# unicorder-temp-mk-2_1.net
KiCad netlist of a schematic drawn in EAGLE
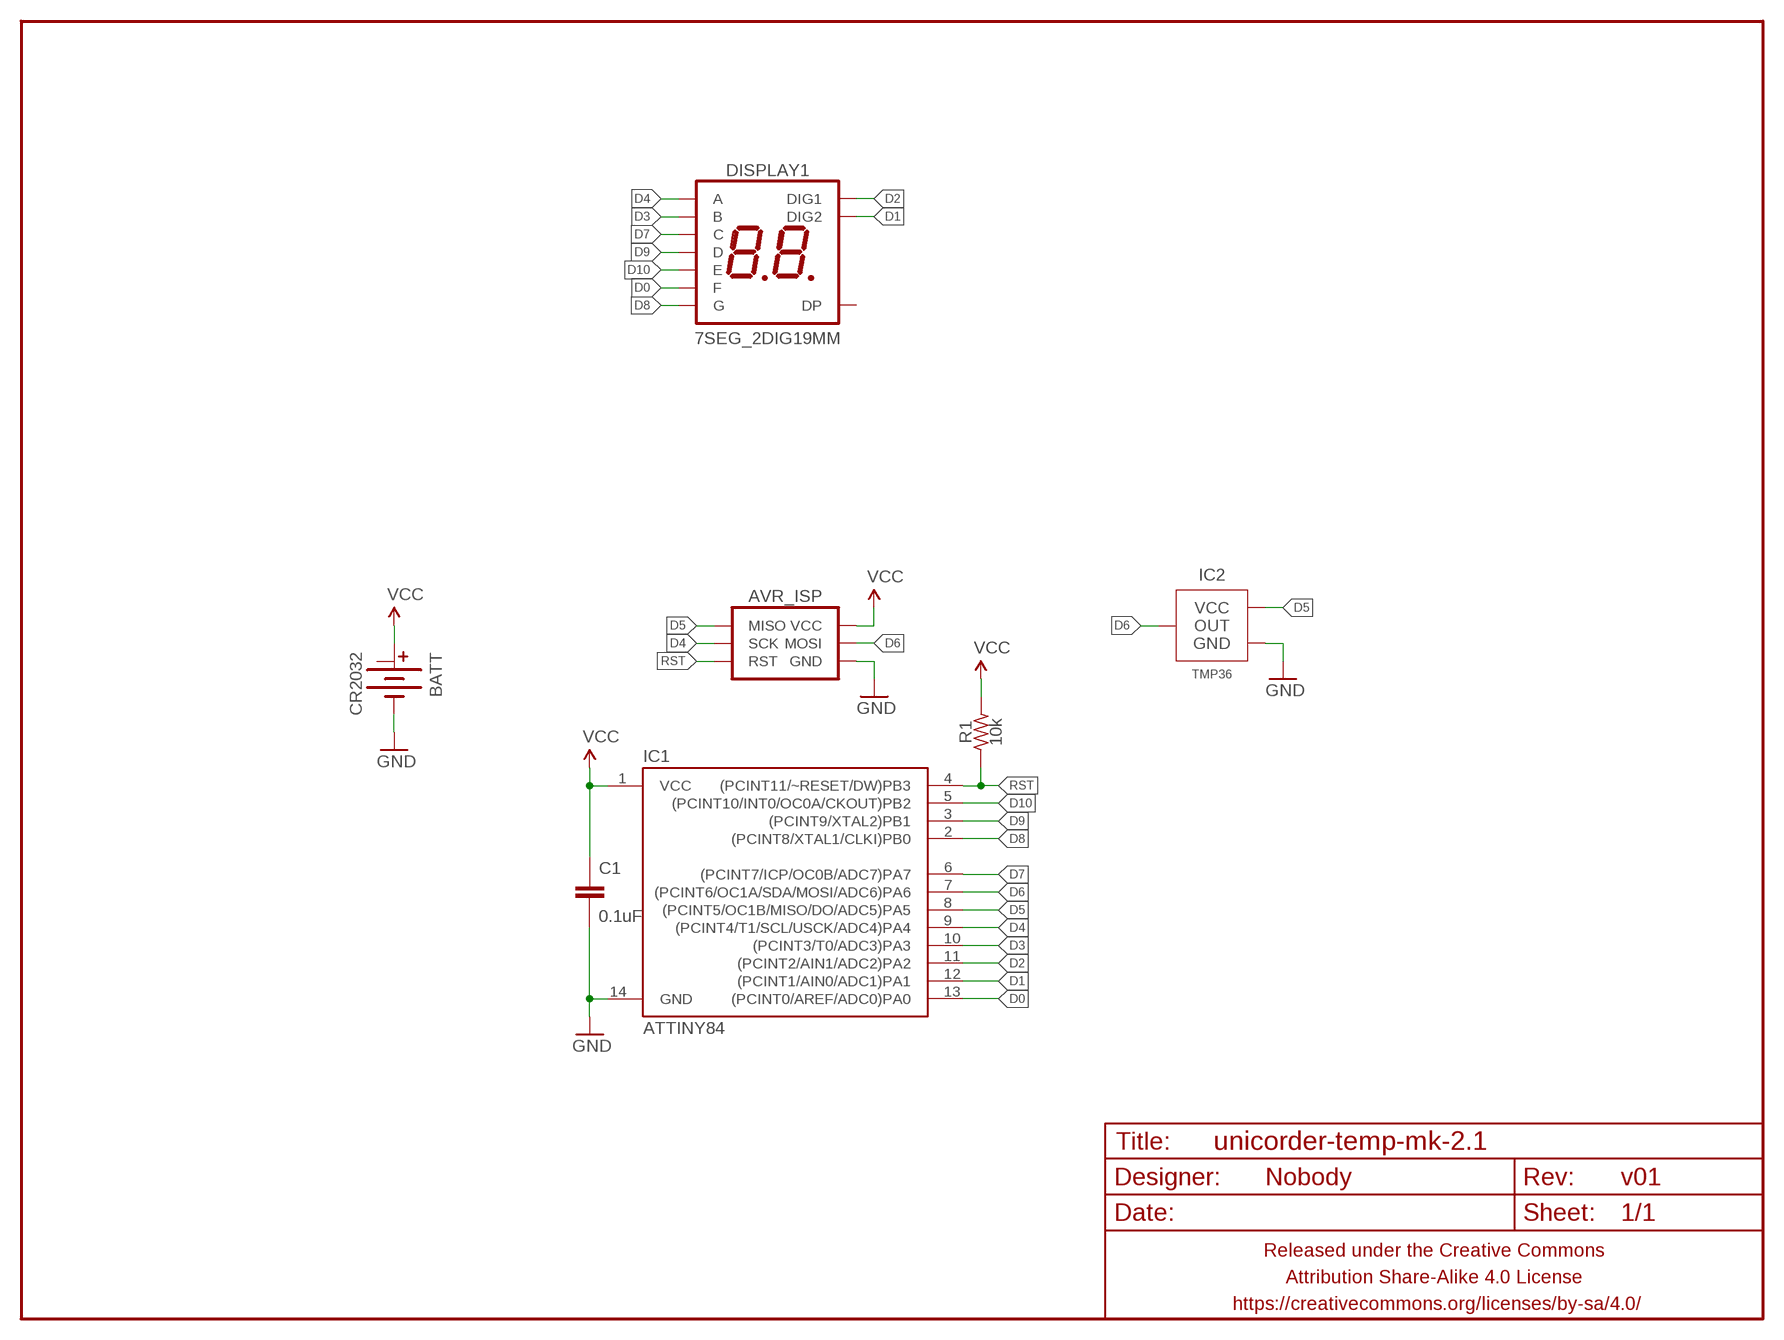
[diagram p0: schematic, sheet 1]

(export (version "E")
  (design (tool "Eeschema 10.0.6"))
  (components
    (comp (ref "AVR_ISP")
      (value "AVR_SPI_PRG_6JST-PH-VERT-PTH")
      (footprint "eagle-import:JST-6-PH-VERT-PTH")
      (libsource (lib "eagle-import") (part "AVR_SPI_PRG_6JST-PH-VERT-PTH"))
    )
    (comp (ref "BATT")
      (value "CR2032")
      (footprint "eagle-import:BATTCON_20MM_MINE")
      (libsource (lib "eagle-import") (part "BATTERY-COINCR2032_SMD"))
    )
    (comp (ref "C1")
      (value "0.1uF")
      (footprint "eagle-import:C025-024X044")
      (libsource (lib "eagle-import") (part "CAPACITOR-CERAMIC025-024X044"))
    )
    (comp (ref "DISPLAY1")
      (value "7SEG_2DIG19MM")
      (footprint "eagle-import:7SEG_2DIG_19MM")
      (libsource (lib "eagle-import") (part "7SEG_2DIG19MM"))
    )
    (comp (ref "FRAME1")
      (value "FRAME-LETTERNO_PACKAGE")
      (footprint "eagle-import:DUMMY")
      (fields (field (name "DESIGNER") "Nobody"))
      (libsource (lib "eagle-import") (part "FRAME-LETTERNO_PACKAGE"))
    )
    (comp (ref "IC1")
      (value "ATTINY84")
      (footprint "eagle-import:DIL14")
      (libsource (lib "eagle-import") (part "ATTINY84ATTINY84-20PU"))
    )
    (comp (ref "IC2")
      (value "TMP36")
      (footprint "eagle-import:TO-92-AMMO")
      (libsource (lib "eagle-import") (part "TMP36TO-92"))
    )
    (comp (ref "R1")
      (value "10k")
      (footprint "eagle-import:RESISTOR-AXIAL-PTH-7.62MM")
      (libsource (lib "eagle-import") (part "RESISTORPTH-AXIAL-7.62MM"))
    )
  )
  (nets
    (net (code "1") (name "D0") (class "Default")
      (node (ref "DISPLAY1") (pin "6") (pinfunction "F_6") (pintype "passive"))
      (node (ref "IC1") (pin "13") (pinfunction "(PCINT0/AREF/ADC0)PA0_13") (pintype "bidirectional"))
    )
    (net (code "2") (name "D1") (class "Default")
      (node (ref "DISPLAY1") (pin "7") (pinfunction "DIG2_7") (pintype "passive"))
      (node (ref "IC1") (pin "12") (pinfunction "(PCINT1/AIN0/ADC1)PA1_12") (pintype "bidirectional"))
    )
    (net (code "3") (name "D2") (class "Default")
      (node (ref "DISPLAY1") (pin "8") (pinfunction "DIG1_8") (pintype "passive"))
      (node (ref "IC1") (pin "11") (pinfunction "(PCINT2/AIN1/ADC2)PA2_11") (pintype "bidirectional"))
    )
    (net (code "4") (name "D3") (class "Default")
      (node (ref "DISPLAY1") (pin "9") (pinfunction "B_9") (pintype "passive"))
      (node (ref "IC1") (pin "10") (pinfunction "(PCINT3/T0/ADC3)PA3_10") (pintype "bidirectional"))
    )
    (net (code "5") (name "D4") (class "Default")
      (node (ref "AVR_ISP") (pin "3") (pinfunction "SCK_3") (pintype "passive"))
      (node (ref "DISPLAY1") (pin "10") (pinfunction "A_10") (pintype "passive"))
      (node (ref "IC1") (pin "9") (pinfunction "(PCINT4/T1/SCL/USCK/ADC4)PA4_9") (pintype "bidirectional"))
    )
    (net (code "6") (name "D5") (class "Default")
      (node (ref "AVR_ISP") (pin "1") (pinfunction "MISO_1") (pintype "passive"))
      (node (ref "IC1") (pin "8") (pinfunction "(PCINT5/OC1B/MISO/DO/ADC5)PA5_8") (pintype "bidirectional"))
      (node (ref "IC2") (pin "1") (pinfunction "VCC_1") (pintype "bidirectional"))
    )
    (net (code "7") (name "D6") (class "Default")
      (node (ref "AVR_ISP") (pin "4") (pinfunction "MOSI_4") (pintype "passive"))
      (node (ref "IC1") (pin "7") (pinfunction "(PCINT6/OC1A/SDA/MOSI/ADC6)PA6_7") (pintype "bidirectional"))
      (node (ref "IC2") (pin "2") (pinfunction "OUT_2") (pintype "bidirectional"))
    )
    (net (code "8") (name "D7") (class "Default")
      (node (ref "DISPLAY1") (pin "1") (pinfunction "C_1") (pintype "passive"))
      (node (ref "IC1") (pin "6") (pinfunction "(PCINT7/ICP/OC0B/ADC7)PA7_6") (pintype "bidirectional"))
    )
    (net (code "9") (name "D8") (class "Default")
      (node (ref "DISPLAY1") (pin "5") (pinfunction "G_5") (pintype "passive"))
      (node (ref "IC1") (pin "2") (pinfunction "(PCINT8/XTAL1/CLKI)PB0_2") (pintype "bidirectional"))
    )
    (net (code "10") (name "D9") (class "Default")
      (node (ref "DISPLAY1") (pin "4") (pinfunction "D_4") (pintype "passive"))
      (node (ref "IC1") (pin "3") (pinfunction "(PCINT9/XTAL2)PB1_3") (pintype "bidirectional"))
    )
    (net (code "11") (name "D10") (class "Default")
      (node (ref "DISPLAY1") (pin "3") (pinfunction "E_3") (pintype "passive"))
      (node (ref "IC1") (pin "5") (pinfunction "(PCINT10/INT0/OC0A/CKOUT)PB2_5") (pintype "bidirectional"))
    )
    (net (code "12") (name "GND") (class "Default")
      (node (ref "AVR_ISP") (pin "6") (pinfunction "GND_6") (pintype "passive"))
      (node (ref "BATT") (pin "BOTTOM") (pinfunction "-_BOTTOM") (pintype "bidirectional"))
      (node (ref "C1") (pin "2") (pinfunction "2_2") (pintype "passive"))
      (node (ref "IC1") (pin "14") (pinfunction "GND_14") (pintype "bidirectional"))
      (node (ref "IC2") (pin "3") (pinfunction "GND_3") (pintype "bidirectional"))
    )
    (net (code "13") (name "RST") (class "Default")
      (node (ref "AVR_ISP") (pin "5") (pinfunction "RST_5") (pintype "passive"))
      (node (ref "IC1") (pin "4") (pinfunction "(PCINT11/~{RESET/DW})PB3_4") (pintype "bidirectional"))
      (node (ref "R1") (pin "P$1") (pinfunction "1_P$1") (pintype "passive"))
    )
    (net (code "14") (name "VCC") (class "Default")
      (node (ref "AVR_ISP") (pin "2") (pinfunction "VCC_2") (pintype "passive"))
      (node (ref "BATT") (pin "TOP@1") (pinfunction "+_TOP@1") (pintype "bidirectional"))
      (node (ref "C1") (pin "1") (pinfunction "1_1") (pintype "passive"))
      (node (ref "IC1") (pin "1") (pinfunction "VCC_1") (pintype "bidirectional"))
      (node (ref "R1") (pin "P$2") (pinfunction "2_P$2") (pintype "passive"))
    )
    (net (code "15") (name "unconnected-(BATT-+1-PadTOP@2)") (class "Default")
      (node (ref "BATT") (pin "TOP@2") (pinfunction "+1_TOP@2") (pintype "bidirectional"))
    )
    (net (code "16") (name "unconnected-(DISPLAY1-DP-Pad2)") (class "Default")
      (node (ref "DISPLAY1") (pin "2") (pinfunction "DP_2") (pintype "passive"))
    )
  )
)
